# ProPrj_gd32f103c8t6__2026-03-23.net
KiCad netlist of a schematic drawn in EasyEDA Pro
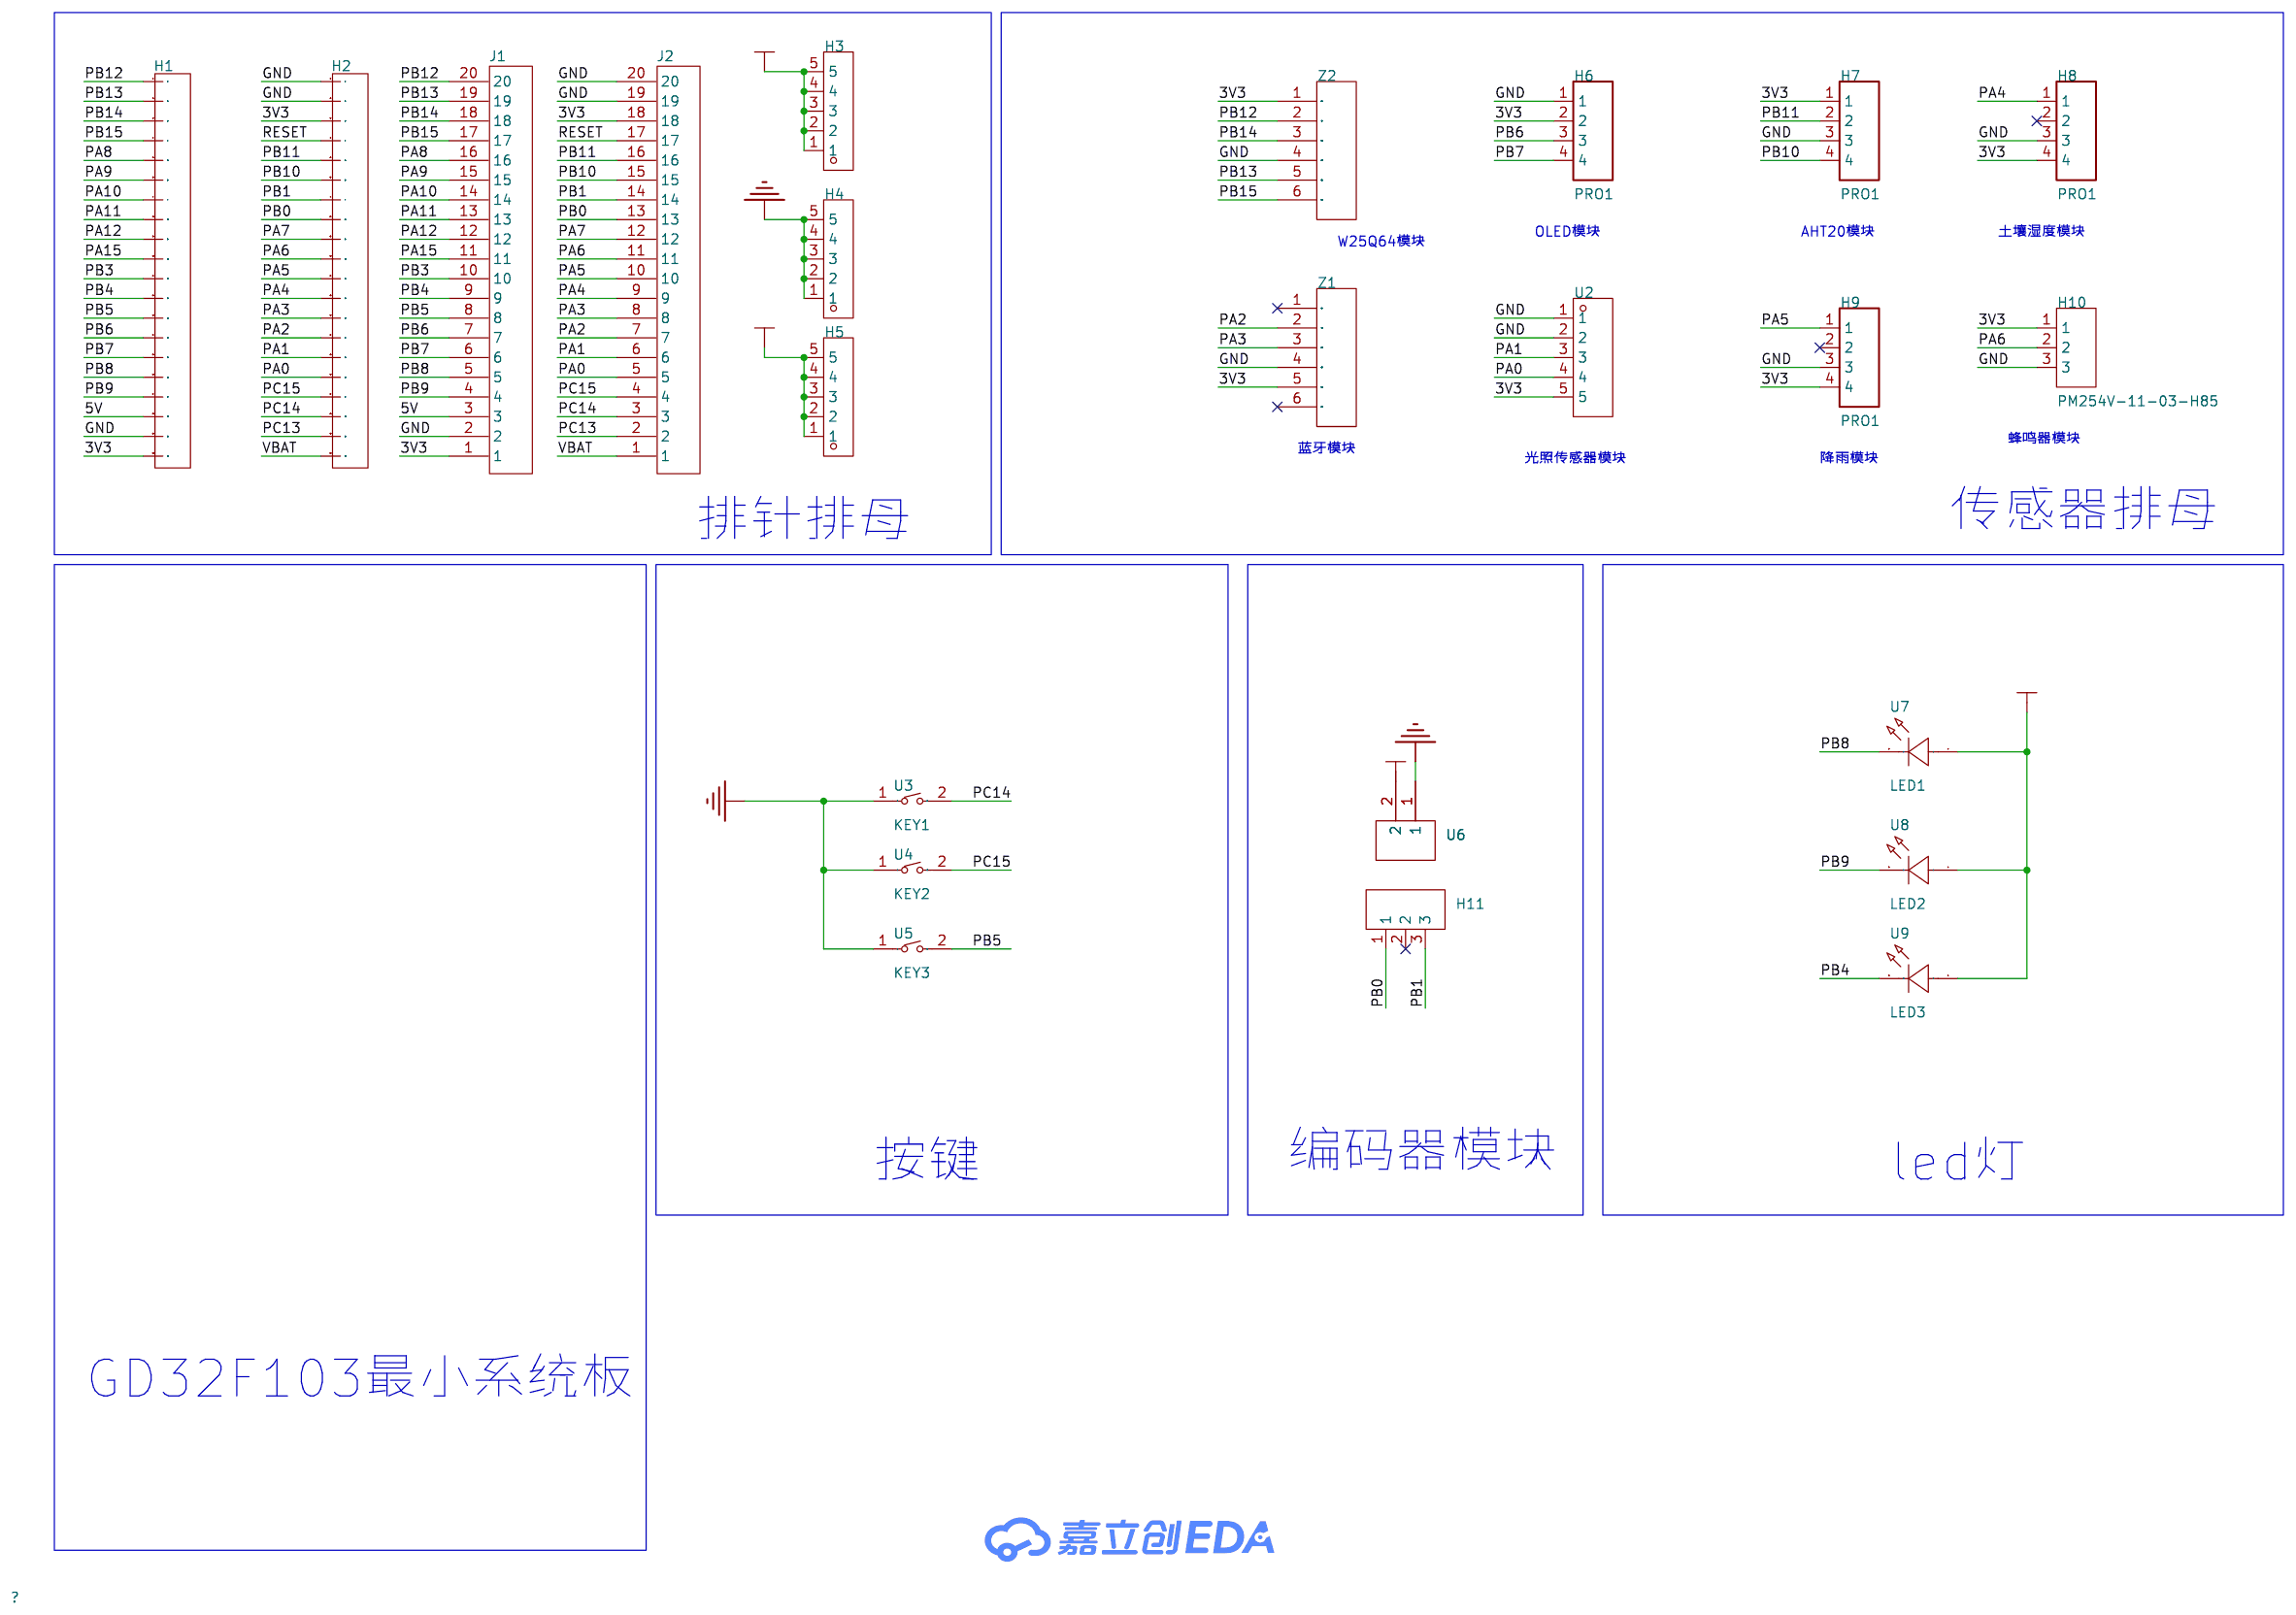
[diagram p0: schematic sheet]

(export (version "E")
  (design (tool "Eeschema 10.0.6"))
  (components
    (comp (ref "H1") (value "~") (footprint "easyedapro:排针20P") (libsource (lib "easyedapro") (part "排针20P")))
    (comp (ref "H2") (value "~") (footprint "easyedapro:排针20P") (libsource (lib "easyedapro") (part "排针20P")))
    (comp (ref "H3")
      (value "~")
      (footprint "easyedapro:5P排针")
      (fields (field (name "Manufacturer Part") "68000-102HLF") (field (name "Manufacturer") "Amphenol ICC"))
      (libsource (lib "easyedapro") (part "5P排针"))
    )
    (comp (ref "H4")
      (value "~")
      (footprint "easyedapro:5P排针")
      (fields (field (name "Manufacturer Part") "68000-102HLF") (field (name "Manufacturer") "Amphenol ICC"))
      (libsource (lib "easyedapro") (part "5P排针"))
    )
    (comp (ref "H5")
      (value "~")
      (footprint "easyedapro:5P排针")
      (fields (field (name "Manufacturer Part") "68000-102HLF") (field (name "Manufacturer") "Amphenol ICC"))
      (libsource (lib "easyedapro") (part "5P排针"))
    )
    (comp (ref "H6")
      (value "PRO1")
      (footprint "easyedapro:HDR-TH_4P-P2.54-V-F")
      (libsource (lib "easyedapro") (part "4P排母"))
    )
    (comp (ref "H7")
      (value "PRO1")
      (footprint "easyedapro:HDR-TH_4P-P2.54-V-F")
      (libsource (lib "easyedapro") (part "4P排母"))
    )
    (comp (ref "H8")
      (value "PRO1")
      (footprint "easyedapro:HDR-TH_4P-P2.54-V-F")
      (libsource (lib "easyedapro") (part "4P排母"))
    )
    (comp (ref "H9")
      (value "PRO1")
      (footprint "easyedapro:HDR-TH_4P-P2.54-V-F")
      (libsource (lib "easyedapro") (part "4P排母"))
    )
    (comp (ref "H10")
      (value "PM254V-11-03-H85")
      (footprint "easyedapro:HDR-TH_3P-P2.54-V-F")
      (fields (field (name "Manufacturer") "XFCN(兴飞)"))
      (libsource (lib "easyedapro") (part "PM254V-11-03-H85"))
    )
    (comp (ref "H11")
      (value "PM254V-11-03-H85")
      (footprint "easyedapro:HDR-TH_3P-P2.54-V-F")
      (fields (field (name "Manufacturer") "XFCN(兴飞)"))
      (libsource (lib "easyedapro") (part "PM254V-11-03-H85"))
    )
    (comp (ref "J1") (value "~") (footprint "easyedapro:20P排针") (libsource (lib "easyedapro") (part "20P排针")))
    (comp (ref "J2") (value "~") (footprint "easyedapro:20P排针") (libsource (lib "easyedapro") (part "20P排针")))
    (comp (ref "U2")
      (value "~")
      (footprint "easyedapro:HDR-TH_5P-P2.54-V-F")
      (libsource (lib "easyedapro") (part "贴片排母5P"))
    )
    (comp (ref "U3")
      (value "KEY1")
      (footprint "easyedapro:KEY-SMD_L6.0-W3.5-LS8.0")
      (fields (field (name "Manufacturer") "Megastar(兆星)"))
      (libsource (lib "easyedapro") (part "ZX-QC36-4.3TPWD"))
    )
    (comp (ref "U4")
      (value "KEY2")
      (footprint "easyedapro:KEY-SMD_L6.0-W3.5-LS8.0")
      (fields (field (name "Manufacturer") "Megastar(兆星)"))
      (libsource (lib "easyedapro") (part "ZX-QC36-4.3TPWD"))
    )
    (comp (ref "U5")
      (value "KEY3")
      (footprint "easyedapro:KEY-SMD_L6.0-W3.5-LS8.0")
      (fields (field (name "Manufacturer") "Megastar(兆星)"))
      (libsource (lib "easyedapro") (part "ZX-QC36-4.3TPWD"))
    )
    (comp (ref "U6") (value "~") (footprint "easyedapro:2P排母封装") (libsource (lib "easyedapro") (part "2P排母")))
    (comp (ref "U7")
      (value "LED1")
      (footprint "easyedapro:LED-TH_BD3.0-P2.54-FD")
      (libsource (lib "easyedapro") (part "3MMFIR"))
    )
    (comp (ref "U8")
      (value "LED2")
      (footprint "easyedapro:LED-TH_BD3.0-P2.54-FD")
      (libsource (lib "easyedapro") (part "3MMFIR"))
    )
    (comp (ref "U9")
      (value "LED3")
      (footprint "easyedapro:LED-TH_BD3.0-P2.54-FD")
      (libsource (lib "easyedapro") (part "3MMFIR"))
    )
    (comp (ref "Z1")
      (value "~")
      (footprint "easyedapro:6P-2.54mm")
      (libsource (lib "easyedapro") (part "排母6P"))
    )
    (comp (ref "Z2")
      (value "~")
      (footprint "easyedapro:6P-2.54mm")
      (libsource (lib "easyedapro") (part "排母6P"))
    )
  )
  (nets
    (net (code "1") (name "/PA0") (class "Default")
      (node (ref "H2") (pin "16") (pinfunction "16_16") (pintype "input"))
      (node (ref "J2") (pin "5") (pinfunction "5_5") (pintype "input"))
      (node (ref "U2") (pin "4") (pinfunction "4_4") (pintype "input"))
    )
    (net (code "2") (name "/PA1") (class "Default")
      (node (ref "H2") (pin "15") (pinfunction "15_15") (pintype "input"))
      (node (ref "J2") (pin "6") (pinfunction "6_6") (pintype "input"))
      (node (ref "U2") (pin "3") (pinfunction "3_3") (pintype "input"))
    )
    (net (code "3") (name "/PA2") (class "Default")
      (node (ref "H2") (pin "14") (pinfunction "14_14") (pintype "input"))
      (node (ref "J2") (pin "7") (pinfunction "7_7") (pintype "input"))
      (node (ref "Z1") (pin "2") (pinfunction "VCC_2") (pintype "input"))
    )
    (net (code "4") (name "/PA3") (class "Default")
      (node (ref "H2") (pin "13") (pinfunction "13_13") (pintype "input"))
      (node (ref "J2") (pin "8") (pinfunction "8_8") (pintype "input"))
      (node (ref "Z1") (pin "3") (pinfunction "GP10_3") (pintype "input"))
    )
    (net (code "5") (name "/PA4") (class "Default")
      (node (ref "H2") (pin "12") (pinfunction "12_12") (pintype "input"))
      (node (ref "H8") (pin "1") (pinfunction "1_1") (pintype "unspecified"))
      (node (ref "J2") (pin "9") (pinfunction "9_9") (pintype "input"))
    )
    (net (code "6") (name "/PA5") (class "Default")
      (node (ref "H2") (pin "11") (pinfunction "11_11") (pintype "input"))
      (node (ref "H9") (pin "1") (pinfunction "1_1") (pintype "unspecified"))
      (node (ref "J2") (pin "10") (pinfunction "10_10") (pintype "input"))
    )
    (net (code "7") (name "/PA6") (class "Default")
      (node (ref "H10") (pin "2") (pinfunction "2_2") (pintype "unspecified"))
      (node (ref "H2") (pin "10") (pinfunction "10_10") (pintype "input"))
      (node (ref "J2") (pin "11") (pinfunction "11_11") (pintype "input"))
    )
    (net (code "8") (name "/PA7") (class "Default")
      (node (ref "H2") (pin "9") (pinfunction "9_9") (pintype "input"))
      (node (ref "J2") (pin "12") (pinfunction "12_12") (pintype "input"))
    )
    (net (code "9") (name "/PA8") (class "Default")
      (node (ref "H1") (pin "5") (pinfunction "5_5") (pintype "input"))
      (node (ref "J1") (pin "16") (pinfunction "16_16") (pintype "input"))
    )
    (net (code "10") (name "/PA9") (class "Default")
      (node (ref "H1") (pin "6") (pinfunction "6_6") (pintype "input"))
      (node (ref "J1") (pin "15") (pinfunction "15_15") (pintype "input"))
    )
    (net (code "11") (name "/PA10") (class "Default")
      (node (ref "H1") (pin "7") (pinfunction "7_7") (pintype "input"))
      (node (ref "J1") (pin "14") (pinfunction "14_14") (pintype "input"))
    )
    (net (code "12") (name "/PA11") (class "Default")
      (node (ref "H1") (pin "8") (pinfunction "8_8") (pintype "input"))
      (node (ref "J1") (pin "13") (pinfunction "13_13") (pintype "input"))
    )
    (net (code "13") (name "/PA12") (class "Default")
      (node (ref "H1") (pin "9") (pinfunction "9_9") (pintype "input"))
      (node (ref "J1") (pin "12") (pinfunction "12_12") (pintype "input"))
    )
    (net (code "14") (name "/PA15") (class "Default")
      (node (ref "H1") (pin "10") (pinfunction "10_10") (pintype "input"))
      (node (ref "J1") (pin "11") (pinfunction "11_11") (pintype "input"))
    )
    (net (code "15") (name "/PB0") (class "Default")
      (node (ref "H11") (pin "1") (pinfunction "1_1") (pintype "unspecified"))
      (node (ref "H2") (pin "8") (pinfunction "8_8") (pintype "input"))
      (node (ref "J2") (pin "13") (pinfunction "13_13") (pintype "input"))
    )
    (net (code "16") (name "/PB1") (class "Default")
      (node (ref "H11") (pin "3") (pinfunction "3_3") (pintype "unspecified"))
      (node (ref "H2") (pin "7") (pinfunction "7_7") (pintype "input"))
      (node (ref "J2") (pin "14") (pinfunction "14_14") (pintype "input"))
    )
    (net (code "17") (name "/PB3") (class "Default")
      (node (ref "H1") (pin "11") (pinfunction "11_11") (pintype "input"))
      (node (ref "J1") (pin "10") (pinfunction "10_10") (pintype "input"))
    )
    (net (code "18") (name "/PB4") (class "Default")
      (node (ref "H1") (pin "12") (pinfunction "12_12") (pintype "input"))
      (node (ref "J1") (pin "9") (pinfunction "9_9") (pintype "input"))
      (node (ref "U9") (pin "2") (pinfunction "K_2") (pintype "unspecified"))
    )
    (net (code "19") (name "/PB5") (class "Default")
      (node (ref "H1") (pin "13") (pinfunction "13_13") (pintype "input"))
      (node (ref "J1") (pin "8") (pinfunction "8_8") (pintype "input"))
      (node (ref "U5") (pin "2") (pinfunction "2_2") (pintype "unspecified"))
    )
    (net (code "20") (name "/PB6") (class "Default")
      (node (ref "H1") (pin "14") (pinfunction "14_14") (pintype "input"))
      (node (ref "H6") (pin "3") (pinfunction "3_3") (pintype "unspecified"))
      (node (ref "J1") (pin "7") (pinfunction "7_7") (pintype "input"))
    )
    (net (code "21") (name "/PB7") (class "Default")
      (node (ref "H1") (pin "15") (pinfunction "15_15") (pintype "input"))
      (node (ref "H6") (pin "4") (pinfunction "4_4") (pintype "unspecified"))
      (node (ref "J1") (pin "6") (pinfunction "6_6") (pintype "input"))
    )
    (net (code "22") (name "/PB8") (class "Default")
      (node (ref "H1") (pin "16") (pinfunction "16_16") (pintype "input"))
      (node (ref "J1") (pin "5") (pinfunction "5_5") (pintype "input"))
      (node (ref "U7") (pin "2") (pinfunction "K_2") (pintype "unspecified"))
    )
    (net (code "23") (name "/PB9") (class "Default")
      (node (ref "H1") (pin "17") (pinfunction "17_17") (pintype "input"))
      (node (ref "J1") (pin "4") (pinfunction "4_4") (pintype "input"))
      (node (ref "U8") (pin "2") (pinfunction "K_2") (pintype "unspecified"))
    )
    (net (code "24") (name "/PB10") (class "Default")
      (node (ref "H2") (pin "6") (pinfunction "6_6") (pintype "input"))
      (node (ref "H7") (pin "4") (pinfunction "4_4") (pintype "unspecified"))
      (node (ref "J2") (pin "15") (pinfunction "15_15") (pintype "input"))
    )
    (net (code "25") (name "/PB11") (class "Default")
      (node (ref "H2") (pin "5") (pinfunction "5_5") (pintype "input"))
      (node (ref "H7") (pin "2") (pinfunction "2_2") (pintype "unspecified"))
      (node (ref "J2") (pin "16") (pinfunction "16_16") (pintype "input"))
    )
    (net (code "26") (name "/PB12") (class "Default")
      (node (ref "H1") (pin "1") (pinfunction "1_1") (pintype "input"))
      (node (ref "J1") (pin "20") (pinfunction "20_20") (pintype "input"))
      (node (ref "Z2") (pin "2") (pinfunction "VCC_2") (pintype "input"))
    )
    (net (code "27") (name "/PB13") (class "Default")
      (node (ref "H1") (pin "2") (pinfunction "2_2") (pintype "input"))
      (node (ref "J1") (pin "19") (pinfunction "19_19") (pintype "input"))
      (node (ref "Z2") (pin "5") (pinfunction "GP03_5") (pintype "input"))
    )
    (net (code "28") (name "/PB14") (class "Default")
      (node (ref "H1") (pin "3") (pinfunction "3_3") (pintype "input"))
      (node (ref "J1") (pin "18") (pinfunction "18_18") (pintype "input"))
      (node (ref "Z2") (pin "3") (pinfunction "GP10_3") (pintype "input"))
    )
    (net (code "29") (name "/PB15") (class "Default")
      (node (ref "H1") (pin "4") (pinfunction "4_4") (pintype "input"))
      (node (ref "J1") (pin "17") (pinfunction "17_17") (pintype "input"))
      (node (ref "Z2") (pin "6") (pinfunction "GND_6") (pintype "input"))
    )
    (net (code "30") (name "/PC13") (class "Default")
      (node (ref "H2") (pin "19") (pinfunction "19_19") (pintype "input"))
      (node (ref "J2") (pin "2") (pinfunction "2_2") (pintype "input"))
    )
    (net (code "31") (name "/PC14") (class "Default")
      (node (ref "H2") (pin "18") (pinfunction "18_18") (pintype "input"))
      (node (ref "J2") (pin "3") (pinfunction "3_3") (pintype "input"))
      (node (ref "U3") (pin "2") (pinfunction "2_2") (pintype "unspecified"))
    )
    (net (code "32") (name "/PC15") (class "Default")
      (node (ref "H2") (pin "17") (pinfunction "17_17") (pintype "input"))
      (node (ref "J2") (pin "4") (pinfunction "4_4") (pintype "input"))
      (node (ref "U4") (pin "2") (pinfunction "2_2") (pintype "unspecified"))
    )
    (net (code "33") (name "/RESET") (class "Default")
      (node (ref "H2") (pin "4") (pinfunction "4_4") (pintype "input"))
      (node (ref "J2") (pin "17") (pinfunction "17_17") (pintype "input"))
    )
    (net (code "34") (name "/VBAT") (class "Default")
      (node (ref "H2") (pin "20") (pinfunction "20_20") (pintype "input"))
      (node (ref "J2") (pin "1") (pinfunction "1_1") (pintype "input"))
    )
    (net (code "35") (name "3V3") (class "Default")
      (node (ref "H1") (pin "20") (pinfunction "20_20") (pintype "input"))
      (node (ref "H10") (pin "1") (pinfunction "1_1") (pintype "unspecified"))
      (node (ref "H2") (pin "3") (pinfunction "3_3") (pintype "input"))
      (node (ref "H3") (pin "1") (pinfunction "1_1") (pintype "input"))
      (node (ref "H3") (pin "2") (pinfunction "2_2") (pintype "input"))
      (node (ref "H3") (pin "3") (pinfunction "3_3") (pintype "input"))
      (node (ref "H3") (pin "4") (pinfunction "4_4") (pintype "input"))
      (node (ref "H3") (pin "5") (pinfunction "5_5") (pintype "input"))
      (node (ref "H6") (pin "2") (pinfunction "2_2") (pintype "unspecified"))
      (node (ref "H7") (pin "1") (pinfunction "1_1") (pintype "unspecified"))
      (node (ref "H8") (pin "4") (pinfunction "4_4") (pintype "unspecified"))
      (node (ref "H9") (pin "4") (pinfunction "4_4") (pintype "unspecified"))
      (node (ref "J1") (pin "1") (pinfunction "1_1") (pintype "input"))
      (node (ref "J2") (pin "18") (pinfunction "18_18") (pintype "input"))
      (node (ref "U2") (pin "5") (pinfunction "5_5") (pintype "input"))
      (node (ref "U6") (pin "2") (pinfunction "2_2") (pintype "input"))
      (node (ref "U7") (pin "1") (pinfunction "A_1") (pintype "unspecified"))
      (node (ref "U8") (pin "1") (pinfunction "A_1") (pintype "unspecified"))
      (node (ref "U9") (pin "1") (pinfunction "A_1") (pintype "unspecified"))
      (node (ref "Z1") (pin "5") (pinfunction "GP03_5") (pintype "input"))
      (node (ref "Z2") (pin "1") (pinfunction "GND_1") (pintype "input"))
    )
    (net (code "36") (name "5V") (class "Default")
      (node (ref "H1") (pin "18") (pinfunction "18_18") (pintype "input"))
      (node (ref "H5") (pin "1") (pinfunction "1_1") (pintype "input"))
      (node (ref "H5") (pin "2") (pinfunction "2_2") (pintype "input"))
      (node (ref "H5") (pin "3") (pinfunction "3_3") (pintype "input"))
      (node (ref "H5") (pin "4") (pinfunction "4_4") (pintype "input"))
      (node (ref "H5") (pin "5") (pinfunction "5_5") (pintype "input"))
      (node (ref "J1") (pin "3") (pinfunction "3_3") (pintype "input"))
    )
    (net (code "37") (name "GND") (class "Default")
      (node (ref "H1") (pin "19") (pinfunction "19_19") (pintype "input"))
      (node (ref "H10") (pin "3") (pinfunction "3_3") (pintype "unspecified"))
      (node (ref "H2") (pin "1") (pinfunction "1_1") (pintype "input"))
      (node (ref "H2") (pin "2") (pinfunction "2_2") (pintype "input"))
      (node (ref "H4") (pin "1") (pinfunction "1_1") (pintype "input"))
      (node (ref "H4") (pin "2") (pinfunction "2_2") (pintype "input"))
      (node (ref "H4") (pin "3") (pinfunction "3_3") (pintype "input"))
      (node (ref "H4") (pin "4") (pinfunction "4_4") (pintype "input"))
      (node (ref "H4") (pin "5") (pinfunction "5_5") (pintype "input"))
      (node (ref "H6") (pin "1") (pinfunction "1_1") (pintype "unspecified"))
      (node (ref "H7") (pin "3") (pinfunction "3_3") (pintype "unspecified"))
      (node (ref "H8") (pin "3") (pinfunction "3_3") (pintype "unspecified"))
      (node (ref "H9") (pin "3") (pinfunction "3_3") (pintype "unspecified"))
      (node (ref "J1") (pin "2") (pinfunction "2_2") (pintype "input"))
      (node (ref "J2") (pin "19") (pinfunction "19_19") (pintype "input"))
      (node (ref "J2") (pin "20") (pinfunction "20_20") (pintype "input"))
      (node (ref "U2") (pin "1") (pinfunction "1_1") (pintype "input"))
      (node (ref "U2") (pin "2") (pinfunction "2_2") (pintype "input"))
      (node (ref "U3") (pin "1") (pinfunction "1_1") (pintype "unspecified"))
      (node (ref "U4") (pin "1") (pinfunction "1_1") (pintype "unspecified"))
      (node (ref "U5") (pin "1") (pinfunction "1_1") (pintype "unspecified"))
      (node (ref "U6") (pin "1") (pinfunction "1_1") (pintype "input"))
      (node (ref "Z1") (pin "4") (pinfunction "GP02_4") (pintype "input"))
      (node (ref "Z2") (pin "4") (pinfunction "GP02_4") (pintype "input"))
    )
    (net (code "38") (name "unconnected-(H8-Pad2)") (class "Default")
      (node (ref "H8") (pin "2") (pinfunction "2_2") (pintype "unspecified+no_connect"))
    )
    (net (code "39") (name "unconnected-(H9-Pad2)") (class "Default")
      (node (ref "H9") (pin "2") (pinfunction "2_2") (pintype "unspecified+no_connect"))
    )
    (net (code "40") (name "unconnected-(H11-Pad2)") (class "Default")
      (node (ref "H11") (pin "2") (pinfunction "2_2") (pintype "unspecified+no_connect"))
    )
    (net (code "41") (name "unconnected-(Z1-GND-Pad1)") (class "Default")
      (node (ref "Z1") (pin "1") (pinfunction "GND_1") (pintype "input+no_connect"))
    )
    (net (code "42") (name "unconnected-(Z1-GND-Pad6)") (class "Default")
      (node (ref "Z1") (pin "6") (pinfunction "GND_6") (pintype "input+no_connect"))
    )
  )
)
